# DRIVER_8_MOTOR_MEGA_DISTANCE_SENSOR_V1_0.net
KiCad netlist of a schematic drawn in EAGLE
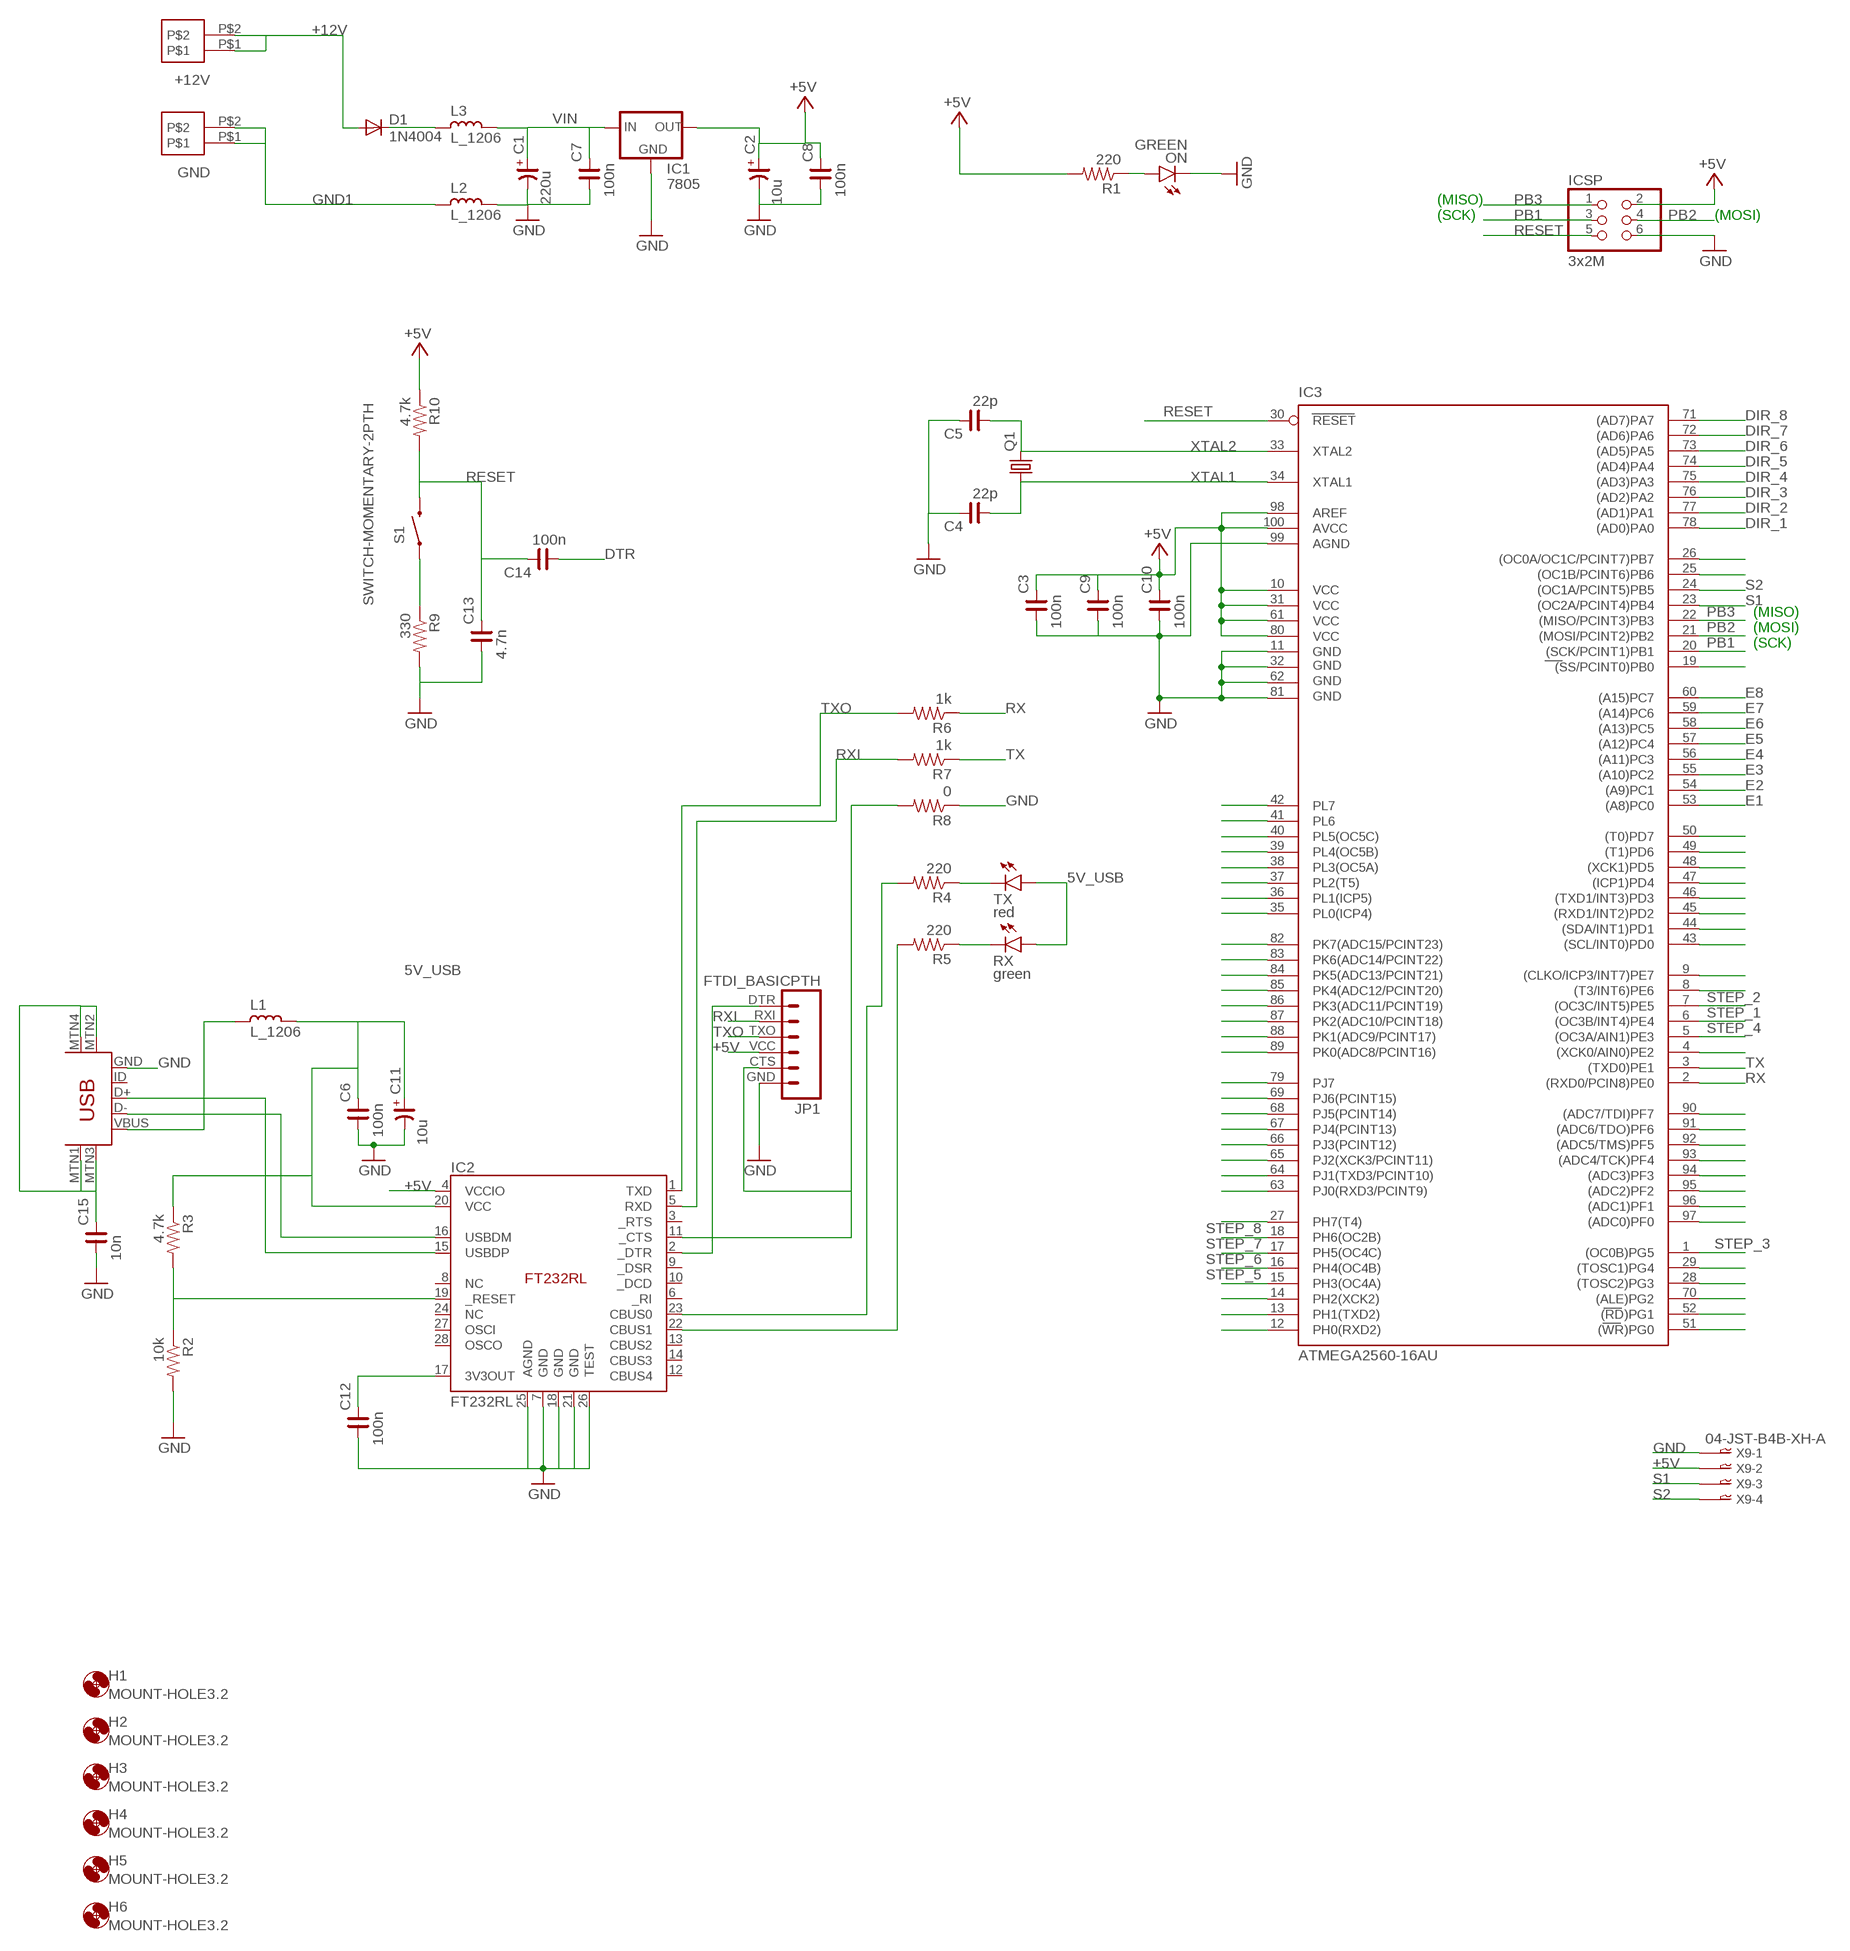
[diagram p0: schematic, sheet 1, part 1 of 2]
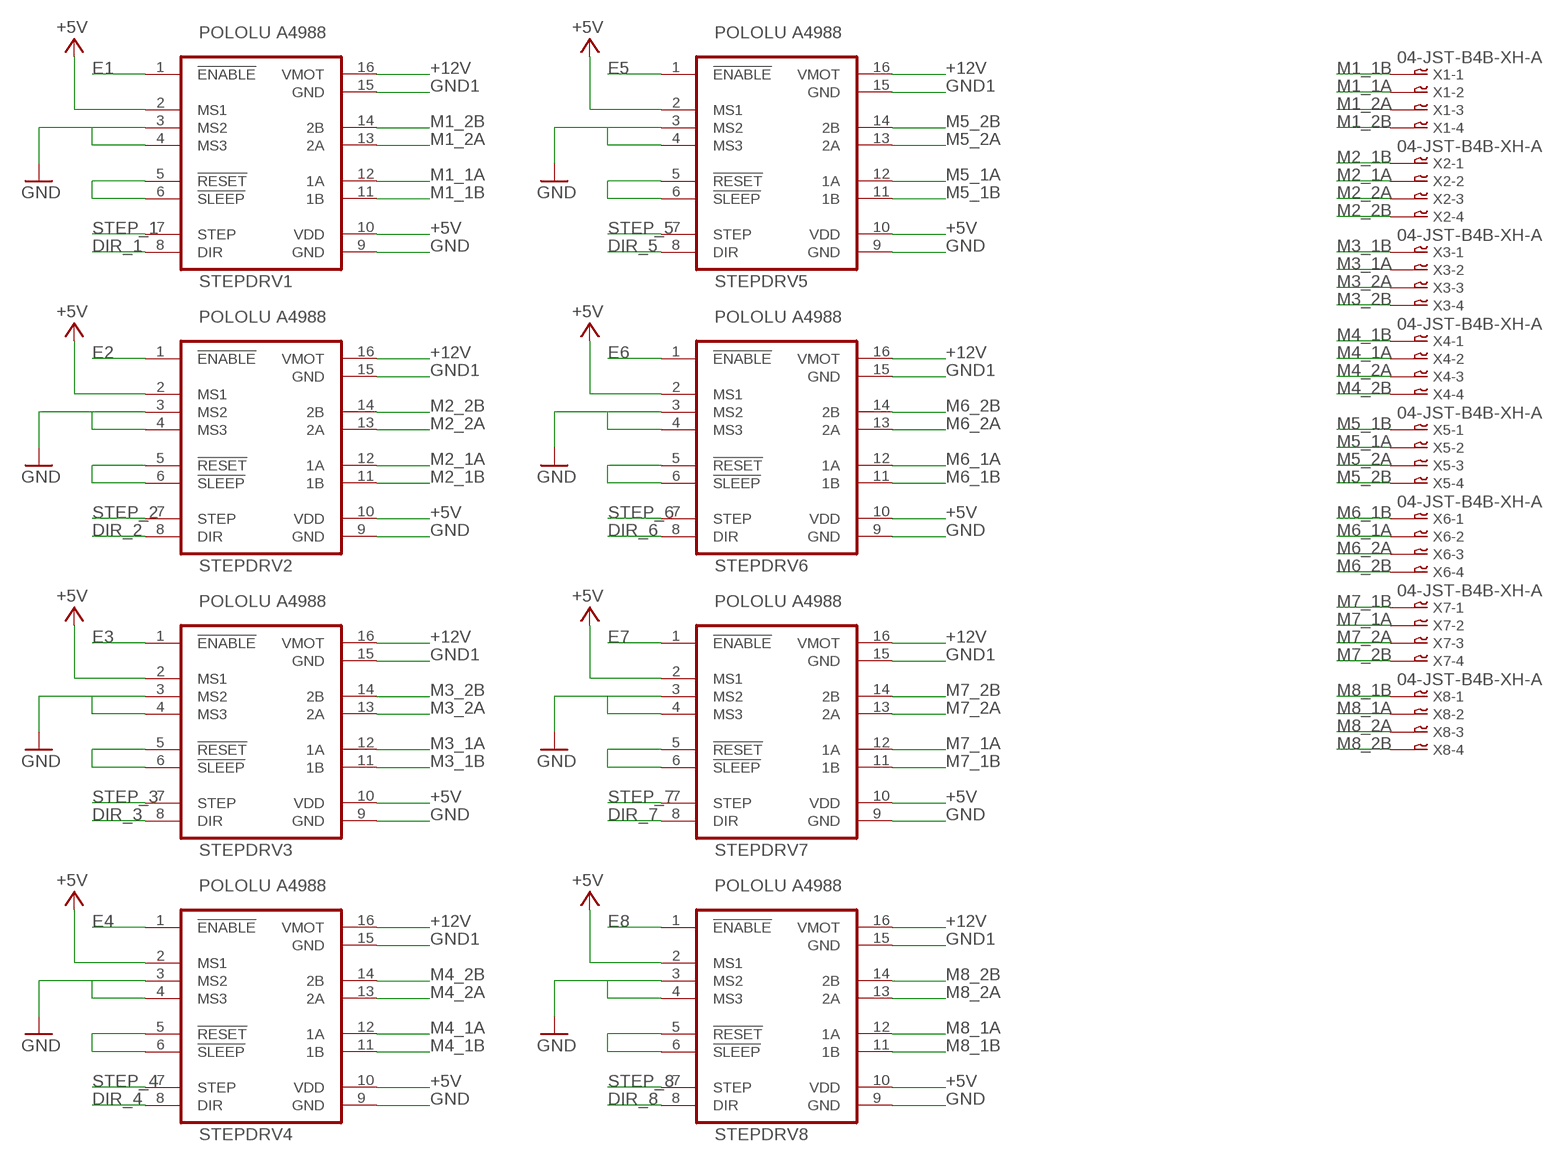
[diagram p1: schematic, sheet 1, part 2 of 2]

(export (version "E")
  (design (tool "Eeschema 10.0.6"))
  (components
    (comp (ref "+12V")
      (value "SCREW_T_10MM")
      (footprint "eagle-import:SCREW_T_10MM")
      (libsource (lib "eagle-import") (part "SCREW_T_10MM"))
    )
    (comp (ref "C1")
      (value "220u")
      (footprint "eagle-import:CE-050X100")
      (libsource (lib "eagle-import") (part "CP_E-050X100"))
    )
    (comp (ref "C2")
      (value "10u")
      (footprint "eagle-import:CE-050X100")
      (libsource (lib "eagle-import") (part "CP_E-050X100"))
    )
    (comp (ref "C3")
      (value "100n")
      (footprint "eagle-import:C050-075X030")
      (libsource (lib "eagle-import") (part "C_C050-075X030"))
    )
    (comp (ref "C4")
      (value "22p")
      (footprint "eagle-import:C050-075X030")
      (libsource (lib "eagle-import") (part "C_C050-075X030"))
    )
    (comp (ref "C5")
      (value "22p")
      (footprint "eagle-import:C050-075X030")
      (libsource (lib "eagle-import") (part "C_C050-075X030"))
    )
    (comp (ref "C6")
      (value "100n")
      (footprint "eagle-import:C050-075X030")
      (libsource (lib "eagle-import") (part "C_C050-075X030"))
    )
    (comp (ref "C7")
      (value "100n")
      (footprint "eagle-import:C050-075X030")
      (libsource (lib "eagle-import") (part "C_C050-075X030"))
    )
    (comp (ref "C8")
      (value "100n")
      (footprint "eagle-import:C050-075X030")
      (libsource (lib "eagle-import") (part "C_C050-075X030"))
    )
    (comp (ref "C9")
      (value "100n")
      (footprint "eagle-import:C050-075X030")
      (libsource (lib "eagle-import") (part "C_C050-075X030"))
    )
    (comp (ref "C10")
      (value "100n")
      (footprint "eagle-import:C050-075X030")
      (libsource (lib "eagle-import") (part "C_C050-075X030"))
    )
    (comp (ref "C11")
      (value "10u")
      (footprint "eagle-import:CE-025X060")
      (libsource (lib "eagle-import") (part "CP_E-025X060"))
    )
    (comp (ref "C12")
      (value "100n")
      (footprint "eagle-import:C050-075X030")
      (libsource (lib "eagle-import") (part "C_C050-075X030"))
    )
    (comp (ref "C13")
      (value "4.7n")
      (footprint "eagle-import:C050-075X030")
      (libsource (lib "eagle-import") (part "C_C050-075X030"))
    )
    (comp (ref "C14")
      (value "100n")
      (footprint "eagle-import:C050-075X030")
      (libsource (lib "eagle-import") (part "C_C050-075X030"))
    )
    (comp (ref "C15")
      (value "10n")
      (footprint "eagle-import:C050-075X030")
      (libsource (lib "eagle-import") (part "C_C050-075X030"))
    )
    (comp (ref "D1")
      (value "1N4004")
      (footprint "eagle-import:DO41-10")
      (libsource (lib "eagle-import") (part "1N4004"))
    )
    (comp (ref "GND")
      (value "SCREW_T_10MM")
      (footprint "eagle-import:SCREW_T_10MM")
      (libsource (lib "eagle-import") (part "SCREW_T_10MM"))
    )
    (comp (ref "H1")
      (value "MOUNT-HOLE3.2")
      (footprint "eagle-import:3,2")
      (libsource (lib "eagle-import") (part "MOUNT-HOLE3.2"))
    )
    (comp (ref "H2")
      (value "MOUNT-HOLE3.2")
      (footprint "eagle-import:3,2")
      (libsource (lib "eagle-import") (part "MOUNT-HOLE3.2"))
    )
    (comp (ref "H3")
      (value "MOUNT-HOLE3.2")
      (footprint "eagle-import:3,2")
      (libsource (lib "eagle-import") (part "MOUNT-HOLE3.2"))
    )
    (comp (ref "H4")
      (value "MOUNT-HOLE3.2")
      (footprint "eagle-import:3,2")
      (libsource (lib "eagle-import") (part "MOUNT-HOLE3.2"))
    )
    (comp (ref "H5")
      (value "MOUNT-HOLE3.2")
      (footprint "eagle-import:3,2")
      (libsource (lib "eagle-import") (part "MOUNT-HOLE3.2"))
    )
    (comp (ref "H6")
      (value "MOUNT-HOLE3.2")
      (footprint "eagle-import:3,2")
      (libsource (lib "eagle-import") (part "MOUNT-HOLE3.2"))
    )
    (comp (ref "IC1")
      (value "7805")
      (footprint "eagle-import:TO-220-ALT")
      (libsource (lib "eagle-import") (part "V_REG_78XX-TO-220"))
    )
    (comp (ref "IC2")
      (value "FT232RL")
      (footprint "eagle-import:SSOP-28")
      (libsource (lib "eagle-import") (part "FT232RL"))
    )
    (comp (ref "IC3")
      (value "ATMEGA2560-16AU")
      (footprint "eagle-import:TQFP100")
      (libsource (lib "eagle-import") (part "ATMEGA2560AU2560-16"))
    )
    (comp (ref "ICSP")
      (value "3x2M")
      (footprint "eagle-import:2X03")
      (libsource (lib "eagle-import") (part "PINHD-2X3"))
    )
    (comp (ref "JP1")
      (value "FTDI_BASICPTH")
      (footprint "eagle-import:FTDI_BASIC")
      (libsource (lib "eagle-import") (part "FTDI_BASICPTH"))
    )
    (comp (ref "L1")
      (value "L_1206")
      (footprint "eagle-import:L1206")
      (libsource (lib "eagle-import") (part "L_1206"))
    )
    (comp (ref "L2")
      (value "L_1206")
      (footprint "eagle-import:L1206")
      (libsource (lib "eagle-import") (part "L_1206"))
    )
    (comp (ref "L3")
      (value "L_1206")
      (footprint "eagle-import:L1206")
      (libsource (lib "eagle-import") (part "L_1206"))
    )
    (comp (ref "ON")
      (value "GREEN")
      (footprint "eagle-import:LED3MM")
      (libsource (lib "eagle-import") (part "LED3MM"))
    )
    (comp (ref "Q1")
      (value "CRYSTALHC49S")
      (footprint "eagle-import:HC49_S")
      (libsource (lib "eagle-import") (part "CRYSTALHC49S"))
    )
    (comp (ref "R1")
      (value "220")
      (footprint "eagle-import:0805")
      (libsource (lib "eagle-import") (part "0.75OHM1/4W1%(0805)"))
    )
    (comp (ref "R2")
      (value "10k")
      (footprint "eagle-import:0805")
      (libsource (lib "eagle-import") (part "0.75OHM1/4W1%(0805)"))
    )
    (comp (ref "R3")
      (value "4.7k")
      (footprint "eagle-import:0805")
      (libsource (lib "eagle-import") (part "0.75OHM1/4W1%(0805)"))
    )
    (comp (ref "R4")
      (value "220")
      (footprint "eagle-import:0805")
      (libsource (lib "eagle-import") (part "0.75OHM1/4W1%(0805)"))
    )
    (comp (ref "R5")
      (value "220")
      (footprint "eagle-import:0805")
      (libsource (lib "eagle-import") (part "0.75OHM1/4W1%(0805)"))
    )
    (comp (ref "R6")
      (value "1k")
      (footprint "eagle-import:0805")
      (libsource (lib "eagle-import") (part "0.75OHM1/4W1%(0805)"))
    )
    (comp (ref "R7")
      (value "1k")
      (footprint "eagle-import:0805")
      (libsource (lib "eagle-import") (part "0.75OHM1/4W1%(0805)"))
    )
    (comp (ref "R8")
      (value "0")
      (footprint "eagle-import:0805")
      (libsource (lib "eagle-import") (part "0.75OHM1/4W1%(0805)"))
    )
    (comp (ref "R9")
      (value "330")
      (footprint "eagle-import:0805")
      (libsource (lib "eagle-import") (part "0.75OHM1/4W1%(0805)"))
    )
    (comp (ref "R10")
      (value "4.7k")
      (footprint "eagle-import:0805")
      (libsource (lib "eagle-import") (part "0.75OHM1/4W1%(0805)"))
    )
    (comp (ref "RX")
      (value "green")
      (footprint "eagle-import:LED3MM")
      (libsource (lib "eagle-import") (part "LED3MM"))
    )
    (comp (ref "S1")
      (value "SWITCH-MOMENTARY-2PTH")
      (footprint "eagle-import:TACTILE-PTH")
      (libsource (lib "eagle-import") (part "SWITCH-MOMENTARY-2PTH"))
    )
    (comp (ref "STEPDRV1")
      (value "POLOLU A4988")
      (footprint "eagle-import:POLOLULU2128")
      (libsource (lib "eagle-import") (part "POLOLULU2128"))
    )
    (comp (ref "STEPDRV2")
      (value "POLOLU A4988")
      (footprint "eagle-import:POLOLULU2128")
      (libsource (lib "eagle-import") (part "POLOLULU2128"))
    )
    (comp (ref "STEPDRV3")
      (value "POLOLU A4988")
      (footprint "eagle-import:POLOLULU2128")
      (libsource (lib "eagle-import") (part "POLOLULU2128"))
    )
    (comp (ref "STEPDRV4")
      (value "POLOLU A4988")
      (footprint "eagle-import:POLOLULU2128")
      (libsource (lib "eagle-import") (part "POLOLULU2128"))
    )
    (comp (ref "STEPDRV5")
      (value "POLOLU A4988")
      (footprint "eagle-import:POLOLULU2128")
      (libsource (lib "eagle-import") (part "POLOLULU2128"))
    )
    (comp (ref "STEPDRV6")
      (value "POLOLU A4988")
      (footprint "eagle-import:POLOLULU2128")
      (libsource (lib "eagle-import") (part "POLOLULU2128"))
    )
    (comp (ref "STEPDRV7")
      (value "POLOLU A4988")
      (footprint "eagle-import:POLOLULU2128")
      (libsource (lib "eagle-import") (part "POLOLULU2128"))
    )
    (comp (ref "STEPDRV8")
      (value "POLOLU A4988")
      (footprint "eagle-import:POLOLULU2128")
      (libsource (lib "eagle-import") (part "POLOLULU2128"))
    )
    (comp (ref "TX")
      (value "red")
      (footprint "eagle-import:LED3MM")
      (libsource (lib "eagle-import") (part "LED3MM"))
    )
    (comp (ref "U$1")
      (value "USB-MINIB-5PIN")
      (footprint "eagle-import:USB-MINIB")
      (libsource (lib "eagle-import") (part "USB-MINIB-5PIN"))
    )
    (comp (ref "X1")
      (value "04-JST-B4B-XH-A")
      (footprint "eagle-import:B4B-XH")
      (libsource (lib "eagle-import") (part "04-JST-B4B-XH-A"))
    )
    (comp (ref "X2")
      (value "04-JST-B4B-XH-A")
      (footprint "eagle-import:B4B-XH")
      (libsource (lib "eagle-import") (part "04-JST-B4B-XH-A"))
    )
    (comp (ref "X3")
      (value "04-JST-B4B-XH-A")
      (footprint "eagle-import:B4B-XH")
      (libsource (lib "eagle-import") (part "04-JST-B4B-XH-A"))
    )
    (comp (ref "X4")
      (value "04-JST-B4B-XH-A")
      (footprint "eagle-import:B4B-XH")
      (libsource (lib "eagle-import") (part "04-JST-B4B-XH-A"))
    )
    (comp (ref "X5")
      (value "04-JST-B4B-XH-A")
      (footprint "eagle-import:B4B-XH")
      (libsource (lib "eagle-import") (part "04-JST-B4B-XH-A"))
    )
    (comp (ref "X6")
      (value "04-JST-B4B-XH-A")
      (footprint "eagle-import:B4B-XH")
      (libsource (lib "eagle-import") (part "04-JST-B4B-XH-A"))
    )
    (comp (ref "X7")
      (value "04-JST-B4B-XH-A")
      (footprint "eagle-import:B4B-XH")
      (libsource (lib "eagle-import") (part "04-JST-B4B-XH-A"))
    )
    (comp (ref "X8")
      (value "04-JST-B4B-XH-A")
      (footprint "eagle-import:B4B-XH")
      (libsource (lib "eagle-import") (part "04-JST-B4B-XH-A"))
    )
    (comp (ref "X9")
      (value "04-JST-B4B-XH-A")
      (footprint "eagle-import:B4B-XH")
      (libsource (lib "eagle-import") (part "04-JST-B4B-XH-A"))
    )
  )
  (nets
    (net (code "1") (name "+5V") (class "Default")
      (node (ref "C10") (pin "2") (pinfunction "2_2") (pintype "passive"))
      (node (ref "C2") (pin "+") (pinfunction "+_+") (pintype "passive"))
      (node (ref "C3") (pin "2") (pinfunction "2_2") (pintype "passive"))
      (node (ref "C8") (pin "2") (pinfunction "2_2") (pintype "passive"))
      (node (ref "C9") (pin "2") (pinfunction "2_2") (pintype "passive"))
      (node (ref "IC1") (pin "OUT") (pinfunction "OUT_OUT") (pintype "output"))
      (node (ref "IC2") (pin "4") (pinfunction "VCCIO_4") (pintype "power_in"))
      (node (ref "IC3") (pin "10") (pinfunction "VCC_10") (pintype "power_in"))
      (node (ref "IC3") (pin "100") (pinfunction "AVCC_100") (pintype "power_in"))
      (node (ref "IC3") (pin "31") (pinfunction "VCC1_31") (pintype "power_in"))
      (node (ref "IC3") (pin "61") (pinfunction "VCC2_61") (pintype "power_in"))
      (node (ref "IC3") (pin "80") (pinfunction "VCC3_80") (pintype "power_in"))
      (node (ref "IC3") (pin "98") (pinfunction "AREF_98") (pintype "bidirectional"))
      (node (ref "ICSP") (pin "2") (pinfunction "2_2") (pintype "passive"))
      (node (ref "JP1") (pin "VCC") (pinfunction "4_VCC") (pintype "passive"))
      (node (ref "R1") (pin "2") (pinfunction "2_2") (pintype "passive"))
      (node (ref "R10") (pin "1") (pinfunction "1_1") (pintype "passive"))
      (node (ref "STEPDRV1") (pin "10") (pinfunction "VDD_10") (pintype "power_in"))
      (node (ref "STEPDRV1") (pin "2") (pinfunction "MS1_2") (pintype "input"))
      (node (ref "STEPDRV2") (pin "10") (pinfunction "VDD_10") (pintype "power_in"))
      (node (ref "STEPDRV2") (pin "2") (pinfunction "MS1_2") (pintype "input"))
      (node (ref "STEPDRV3") (pin "10") (pinfunction "VDD_10") (pintype "power_in"))
      (node (ref "STEPDRV3") (pin "2") (pinfunction "MS1_2") (pintype "input"))
      (node (ref "STEPDRV4") (pin "10") (pinfunction "VDD_10") (pintype "power_in"))
      (node (ref "STEPDRV4") (pin "2") (pinfunction "MS1_2") (pintype "input"))
      (node (ref "STEPDRV5") (pin "10") (pinfunction "VDD_10") (pintype "power_in"))
      (node (ref "STEPDRV5") (pin "2") (pinfunction "MS1_2") (pintype "input"))
      (node (ref "STEPDRV6") (pin "10") (pinfunction "VDD_10") (pintype "power_in"))
      (node (ref "STEPDRV6") (pin "2") (pinfunction "MS1_2") (pintype "input"))
      (node (ref "STEPDRV7") (pin "10") (pinfunction "VDD_10") (pintype "power_in"))
      (node (ref "STEPDRV7") (pin "2") (pinfunction "MS1_2") (pintype "input"))
      (node (ref "STEPDRV8") (pin "10") (pinfunction "VDD_10") (pintype "power_in"))
      (node (ref "STEPDRV8") (pin "2") (pinfunction "MS1_2") (pintype "input"))
      (node (ref "X9") (pin "P$2") (pinfunction "1_P$2") (pintype "passive"))
    )
    (net (code "2") (name "/+12V") (class "Default")
      (node (ref "+12V") (pin "P$1") (pinfunction "P$1_P$1") (pintype "bidirectional"))
      (node (ref "+12V") (pin "P$2") (pinfunction "P$2_P$2") (pintype "bidirectional"))
      (node (ref "D1") (pin "A") (pinfunction "A_A") (pintype "passive"))
      (node (ref "STEPDRV1") (pin "16") (pinfunction "VMOT_16") (pintype "power_in"))
      (node (ref "STEPDRV2") (pin "16") (pinfunction "VMOT_16") (pintype "power_in"))
      (node (ref "STEPDRV3") (pin "16") (pinfunction "VMOT_16") (pintype "power_in"))
      (node (ref "STEPDRV4") (pin "16") (pinfunction "VMOT_16") (pintype "power_in"))
      (node (ref "STEPDRV5") (pin "16") (pinfunction "VMOT_16") (pintype "power_in"))
      (node (ref "STEPDRV6") (pin "16") (pinfunction "VMOT_16") (pintype "power_in"))
      (node (ref "STEPDRV7") (pin "16") (pinfunction "VMOT_16") (pintype "power_in"))
      (node (ref "STEPDRV8") (pin "16") (pinfunction "VMOT_16") (pintype "power_in"))
    )
    (net (code "3") (name "/5V_USB") (class "Default")
      (node (ref "C11") (pin "+") (pinfunction "+_+") (pintype "passive"))
      (node (ref "C6") (pin "2") (pinfunction "2_2") (pintype "passive"))
      (node (ref "IC2") (pin "20") (pinfunction "VCC_20") (pintype "power_in"))
      (node (ref "L1") (pin "1") (pinfunction "1_1") (pintype "passive"))
      (node (ref "R3") (pin "1") (pinfunction "1_1") (pintype "passive"))
      (node (ref "RX") (pin "A") (pinfunction "A_A") (pintype "passive"))
      (node (ref "TX") (pin "A") (pinfunction "A_A") (pintype "passive"))
    )
    (net (code "4") (name "/DIR_1") (class "Default")
      (node (ref "IC3") (pin "78") (pinfunction "(AD0)PA0_78") (pintype "bidirectional"))
      (node (ref "STEPDRV1") (pin "8") (pinfunction "DIR_8") (pintype "input"))
    )
    (net (code "5") (name "/DIR_2") (class "Default")
      (node (ref "IC3") (pin "77") (pinfunction "(AD1)PA1_77") (pintype "bidirectional"))
      (node (ref "STEPDRV2") (pin "8") (pinfunction "DIR_8") (pintype "input"))
    )
    (net (code "6") (name "/DIR_3") (class "Default")
      (node (ref "IC3") (pin "76") (pinfunction "(AD2)PA2_76") (pintype "bidirectional"))
      (node (ref "STEPDRV3") (pin "8") (pinfunction "DIR_8") (pintype "input"))
    )
    (net (code "7") (name "/DIR_4") (class "Default")
      (node (ref "IC3") (pin "75") (pinfunction "(AD3)PA3_75") (pintype "bidirectional"))
      (node (ref "STEPDRV4") (pin "8") (pinfunction "DIR_8") (pintype "input"))
    )
    (net (code "8") (name "/DIR_5") (class "Default")
      (node (ref "IC3") (pin "74") (pinfunction "(AD4)PA4_74") (pintype "bidirectional"))
      (node (ref "STEPDRV5") (pin "8") (pinfunction "DIR_8") (pintype "input"))
    )
    (net (code "9") (name "/DIR_6") (class "Default")
      (node (ref "IC3") (pin "73") (pinfunction "(AD5)PA5_73") (pintype "bidirectional"))
      (node (ref "STEPDRV6") (pin "8") (pinfunction "DIR_8") (pintype "input"))
    )
    (net (code "10") (name "/DIR_7") (class "Default")
      (node (ref "IC3") (pin "72") (pinfunction "(AD6)PA6_72") (pintype "bidirectional"))
      (node (ref "STEPDRV7") (pin "8") (pinfunction "DIR_8") (pintype "input"))
    )
    (net (code "11") (name "/DIR_8") (class "Default")
      (node (ref "IC3") (pin "71") (pinfunction "(AD7)PA7_71") (pintype "bidirectional"))
      (node (ref "STEPDRV8") (pin "8") (pinfunction "DIR_8") (pintype "input"))
    )
    (net (code "12") (name "/DTR") (class "Default")
      (node (ref "C14") (pin "1") (pinfunction "1_1") (pintype "passive"))
      (node (ref "IC2") (pin "2") (pinfunction "_DTR_2") (pintype "input"))
      (node (ref "JP1") (pin "DTR") (pinfunction "1_DTR") (pintype "passive"))
    )
    (net (code "13") (name "/E1") (class "Default")
      (node (ref "IC3") (pin "53") (pinfunction "(A8)PC0_53") (pintype "bidirectional"))
      (node (ref "STEPDRV1") (pin "1") (pinfunction "~{ENABLE}_1") (pintype "input"))
    )
    (net (code "14") (name "/E2") (class "Default")
      (node (ref "IC3") (pin "54") (pinfunction "(A9)PC1_54") (pintype "bidirectional"))
      (node (ref "STEPDRV2") (pin "1") (pinfunction "~{ENABLE}_1") (pintype "input"))
    )
    (net (code "15") (name "/E3") (class "Default")
      (node (ref "IC3") (pin "55") (pinfunction "(A10)PC2_55") (pintype "bidirectional"))
      (node (ref "STEPDRV3") (pin "1") (pinfunction "~{ENABLE}_1") (pintype "input"))
    )
    (net (code "16") (name "/E4") (class "Default")
      (node (ref "IC3") (pin "56") (pinfunction "(A11)PC3_56") (pintype "bidirectional"))
      (node (ref "STEPDRV4") (pin "1") (pinfunction "~{ENABLE}_1") (pintype "input"))
    )
    (net (code "17") (name "/E5") (class "Default")
      (node (ref "IC3") (pin "57") (pinfunction "(A12)PC4_57") (pintype "bidirectional"))
      (node (ref "STEPDRV5") (pin "1") (pinfunction "~{ENABLE}_1") (pintype "input"))
    )
    (net (code "18") (name "/E6") (class "Default")
      (node (ref "IC3") (pin "58") (pinfunction "(A13)PC5_58") (pintype "bidirectional"))
      (node (ref "STEPDRV6") (pin "1") (pinfunction "~{ENABLE}_1") (pintype "input"))
    )
    (net (code "19") (name "/E7") (class "Default")
      (node (ref "IC3") (pin "59") (pinfunction "(A14)PC6_59") (pintype "bidirectional"))
      (node (ref "STEPDRV7") (pin "1") (pinfunction "~{ENABLE}_1") (pintype "input"))
    )
    (net (code "20") (name "/E8") (class "Default")
      (node (ref "IC3") (pin "60") (pinfunction "(A15)PC7_60") (pintype "bidirectional"))
      (node (ref "STEPDRV8") (pin "1") (pinfunction "~{ENABLE}_1") (pintype "input"))
    )
    (net (code "21") (name "/GND1") (class "Default")
      (node (ref "GND") (pin "P$1") (pinfunction "P$1_P$1") (pintype "bidirectional"))
      (node (ref "GND") (pin "P$2") (pinfunction "P$2_P$2") (pintype "bidirectional"))
      (node (ref "L2") (pin "2") (pinfunction "2_2") (pintype "passive"))
      (node (ref "STEPDRV1") (pin "15") (pinfunction "GND_15") (pintype "power_in"))
      (node (ref "STEPDRV2") (pin "15") (pinfunction "GND_15") (pintype "power_in"))
      (node (ref "STEPDRV3") (pin "15") (pinfunction "GND_15") (pintype "power_in"))
      (node (ref "STEPDRV4") (pin "15") (pinfunction "GND_15") (pintype "power_in"))
      (node (ref "STEPDRV5") (pin "15") (pinfunction "GND_15") (pintype "power_in"))
      (node (ref "STEPDRV6") (pin "15") (pinfunction "GND_15") (pintype "power_in"))
      (node (ref "STEPDRV7") (pin "15") (pinfunction "GND_15") (pintype "power_in"))
      (node (ref "STEPDRV8") (pin "15") (pinfunction "GND_15") (pintype "power_in"))
    )
    (net (code "22") (name "/M1_1A") (class "Default")
      (node (ref "STEPDRV1") (pin "12") (pinfunction "1A_12") (pintype "output"))
      (node (ref "X1") (pin "P$2") (pinfunction "1_P$2") (pintype "passive"))
    )
    (net (code "23") (name "/M1_1B") (class "Default")
      (node (ref "STEPDRV1") (pin "11") (pinfunction "1B_11") (pintype "output"))
      (node (ref "X1") (pin "P$1") (pinfunction "1_P$1") (pintype "passive"))
    )
    (net (code "24") (name "/M1_2A") (class "Default")
      (node (ref "STEPDRV1") (pin "13") (pinfunction "2A_13") (pintype "output"))
      (node (ref "X1") (pin "P$3") (pinfunction "1_P$3") (pintype "passive"))
    )
    (net (code "25") (name "/M1_2B") (class "Default")
      (node (ref "STEPDRV1") (pin "14") (pinfunction "2B_14") (pintype "output"))
      (node (ref "X1") (pin "P$4") (pinfunction "1_P$4") (pintype "passive"))
    )
    (net (code "26") (name "/M2_1A") (class "Default")
      (node (ref "STEPDRV2") (pin "12") (pinfunction "1A_12") (pintype "output"))
      (node (ref "X2") (pin "P$2") (pinfunction "1_P$2") (pintype "passive"))
    )
    (net (code "27") (name "/M2_1B") (class "Default")
      (node (ref "STEPDRV2") (pin "11") (pinfunction "1B_11") (pintype "output"))
      (node (ref "X2") (pin "P$1") (pinfunction "1_P$1") (pintype "passive"))
    )
    (net (code "28") (name "/M2_2A") (class "Default")
      (node (ref "STEPDRV2") (pin "13") (pinfunction "2A_13") (pintype "output"))
      (node (ref "X2") (pin "P$3") (pinfunction "1_P$3") (pintype "passive"))
    )
    (net (code "29") (name "/M2_2B") (class "Default")
      (node (ref "STEPDRV2") (pin "14") (pinfunction "2B_14") (pintype "output"))
      (node (ref "X2") (pin "P$4") (pinfunction "1_P$4") (pintype "passive"))
    )
    (net (code "30") (name "/M3_1A") (class "Default")
      (node (ref "STEPDRV3") (pin "12") (pinfunction "1A_12") (pintype "output"))
      (node (ref "X3") (pin "P$2") (pinfunction "1_P$2") (pintype "passive"))
    )
    (net (code "31") (name "/M3_1B") (class "Default")
      (node (ref "STEPDRV3") (pin "11") (pinfunction "1B_11") (pintype "output"))
      (node (ref "X3") (pin "P$1") (pinfunction "1_P$1") (pintype "passive"))
    )
    (net (code "32") (name "/M3_2A") (class "Default")
      (node (ref "STEPDRV3") (pin "13") (pinfunction "2A_13") (pintype "output"))
      (node (ref "X3") (pin "P$3") (pinfunction "1_P$3") (pintype "passive"))
    )
    (net (code "33") (name "/M3_2B") (class "Default")
      (node (ref "STEPDRV3") (pin "14") (pinfunction "2B_14") (pintype "output"))
      (node (ref "X3") (pin "P$4") (pinfunction "1_P$4") (pintype "passive"))
    )
    (net (code "34") (name "/M4_1A") (class "Default")
      (node (ref "STEPDRV4") (pin "12") (pinfunction "1A_12") (pintype "output"))
      (node (ref "X4") (pin "P$2") (pinfunction "1_P$2") (pintype "passive"))
    )
    (net (code "35") (name "/M4_1B") (class "Default")
      (node (ref "STEPDRV4") (pin "11") (pinfunction "1B_11") (pintype "output"))
      (node (ref "X4") (pin "P$1") (pinfunction "1_P$1") (pintype "passive"))
    )
    (net (code "36") (name "/M4_2A") (class "Default")
      (node (ref "STEPDRV4") (pin "13") (pinfunction "2A_13") (pintype "output"))
      (node (ref "X4") (pin "P$3") (pinfunction "1_P$3") (pintype "passive"))
    )
    (net (code "37") (name "/M4_2B") (class "Default")
      (node (ref "STEPDRV4") (pin "14") (pinfunction "2B_14") (pintype "output"))
      (node (ref "X4") (pin "P$4") (pinfunction "1_P$4") (pintype "passive"))
    )
    (net (code "38") (name "/M5_1A") (class "Default")
      (node (ref "STEPDRV5") (pin "12") (pinfunction "1A_12") (pintype "output"))
      (node (ref "X5") (pin "P$2") (pinfunction "1_P$2") (pintype "passive"))
    )
    (net (code "39") (name "/M5_1B") (class "Default")
      (node (ref "STEPDRV5") (pin "11") (pinfunction "1B_11") (pintype "output"))
      (node (ref "X5") (pin "P$1") (pinfunction "1_P$1") (pintype "passive"))
    )
    (net (code "40") (name "/M5_2A") (class "Default")
      (node (ref "STEPDRV5") (pin "13") (pinfunction "2A_13") (pintype "output"))
      (node (ref "X5") (pin "P$3") (pinfunction "1_P$3") (pintype "passive"))
    )
    (net (code "41") (name "/M5_2B") (class "Default")
      (node (ref "STEPDRV5") (pin "14") (pinfunction "2B_14") (pintype "output"))
      (node (ref "X5") (pin "P$4") (pinfunction "1_P$4") (pintype "passive"))
    )
    (net (code "42") (name "/M6_1A") (class "Default")
      (node (ref "STEPDRV6") (pin "12") (pinfunction "1A_12") (pintype "output"))
      (node (ref "X6") (pin "P$2") (pinfunction "1_P$2") (pintype "passive"))
    )
    (net (code "43") (name "/M6_1B") (class "Default")
      (node (ref "STEPDRV6") (pin "11") (pinfunction "1B_11") (pintype "output"))
      (node (ref "X6") (pin "P$1") (pinfunction "1_P$1") (pintype "passive"))
    )
    (net (code "44") (name "/M6_2A") (class "Default")
      (node (ref "STEPDRV6") (pin "13") (pinfunction "2A_13") (pintype "output"))
      (node (ref "X6") (pin "P$3") (pinfunction "1_P$3") (pintype "passive"))
    )
    (net (code "45") (name "/M6_2B") (class "Default")
      (node (ref "STEPDRV6") (pin "14") (pinfunction "2B_14") (pintype "output"))
      (node (ref "X6") (pin "P$4") (pinfunction "1_P$4") (pintype "passive"))
    )
    (net (code "46") (name "/M7_1A") (class "Default")
      (node (ref "STEPDRV7") (pin "12") (pinfunction "1A_12") (pintype "output"))
      (node (ref "X7") (pin "P$2") (pinfunction "1_P$2") (pintype "passive"))
    )
    (net (code "47") (name "/M7_1B") (class "Default")
      (node (ref "STEPDRV7") (pin "11") (pinfunction "1B_11") (pintype "output"))
      (node (ref "X7") (pin "P$1") (pinfunction "1_P$1") (pintype "passive"))
    )
    (net (code "48") (name "/M7_2A") (class "Default")
      (node (ref "STEPDRV7") (pin "13") (pinfunction "2A_13") (pintype "output"))
      (node (ref "X7") (pin "P$3") (pinfunction "1_P$3") (pintype "passive"))
    )
    (net (code "49") (name "/M7_2B") (class "Default")
      (node (ref "STEPDRV7") (pin "14") (pinfunction "2B_14") (pintype "output"))
      (node (ref "X7") (pin "P$4") (pinfunction "1_P$4") (pintype "passive"))
    )
    (net (code "50") (name "/M8_1A") (class "Default")
      (node (ref "STEPDRV8") (pin "12") (pinfunction "1A_12") (pintype "output"))
      (node (ref "X8") (pin "P$2") (pinfunction "1_P$2") (pintype "passive"))
    )
    (net (code "51") (name "/M8_1B") (class "Default")
      (node (ref "STEPDRV8") (pin "11") (pinfunction "1B_11") (pintype "output"))
      (node (ref "X8") (pin "P$1") (pinfunction "1_P$1") (pintype "passive"))
    )
    (net (code "52") (name "/M8_2A") (class "Default")
      (node (ref "STEPDRV8") (pin "13") (pinfunction "2A_13") (pintype "output"))
      (node (ref "X8") (pin "P$3") (pinfunction "1_P$3") (pintype "passive"))
    )
    (net (code "53") (name "/M8_2B") (class "Default")
      (node (ref "STEPDRV8") (pin "14") (pinfunction "2B_14") (pintype "output"))
      (node (ref "X8") (pin "P$4") (pinfunction "1_P$4") (pintype "passive"))
    )
    (net (code "54") (name "/PB1") (class "Default")
      (node (ref "IC3") (pin "20") (pinfunction "(SCK/PCINT1)PB1_20") (pintype "bidirectional"))
      (node (ref "ICSP") (pin "3") (pinfunction "3_3") (pintype "passive"))
    )
    (net (code "55") (name "/PB2") (class "Default")
      (node (ref "IC3") (pin "21") (pinfunction "(MOSI/PCINT2)PB2_21") (pintype "bidirectional"))
      (node (ref "ICSP") (pin "4") (pinfunction "4_4") (pintype "passive"))
    )
    (net (code "56") (name "/PB3") (class "Default")
      (node (ref "IC3") (pin "22") (pinfunction "(MISO/PCINT3)PB3_22") (pintype "bidirectional"))
      (node (ref "ICSP") (pin "1") (pinfunction "1_1") (pintype "passive"))
    )
    (net (code "57") (name "/RESET") (class "Default")
      (node (ref "C13") (pin "2") (pinfunction "2_2") (pintype "passive"))
      (node (ref "C14") (pin "2") (pinfunction "2_2") (pintype "passive"))
      (node (ref "IC3") (pin "30") (pinfunction "RESET_30") (pintype "input"))
      (node (ref "ICSP") (pin "5") (pinfunction "5_5") (pintype "passive"))
      (node (ref "R10") (pin "2") (pinfunction "2_2") (pintype "passive"))
      (node (ref "S1") (pin "3") (pinfunction "2_3") (pintype "passive"))
    )
    (net (code "58") (name "/RX") (class "Default")
      (node (ref "IC3") (pin "2") (pinfunction "(RXD0/PCIN8)PE0_2") (pintype "bidirectional"))
      (node (ref "R6") (pin "1") (pinfunction "1_1") (pintype "passive"))
    )
    (net (code "59") (name "/RXI") (class "Default")
      (node (ref "IC2") (pin "5") (pinfunction "RXD_5") (pintype "input"))
      (node (ref "JP1") (pin "RXI") (pinfunction "2_RXI") (pintype "passive"))
      (node (ref "R7") (pin "2") (pinfunction "2_2") (pintype "passive"))
    )
    (net (code "60") (name "/S1") (class "Default")
      (node (ref "IC3") (pin "23") (pinfunction "(OC2A/PCINT4)PB4_23") (pintype "bidirectional"))
      (node (ref "X9") (pin "P$3") (pinfunction "1_P$3") (pintype "passive"))
    )
    (net (code "61") (name "/S2") (class "Default")
      (node (ref "IC3") (pin "24") (pinfunction "(OC1A/PCINT5)PB5_24") (pintype "bidirectional"))
      (node (ref "X9") (pin "P$4") (pinfunction "1_P$4") (pintype "passive"))
    )
    (net (code "62") (name "/STEP_1") (class "Default")
      (node (ref "IC3") (pin "6") (pinfunction "(OC3B/INT4)PE4_6") (pintype "bidirectional"))
      (node (ref "STEPDRV1") (pin "7") (pinfunction "STEP_7") (pintype "input"))
    )
    (net (code "63") (name "/STEP_2") (class "Default")
      (node (ref "IC3") (pin "7") (pinfunction "(OC3C/INT5)PE5_7") (pintype "bidirectional"))
      (node (ref "STEPDRV2") (pin "7") (pinfunction "STEP_7") (pintype "input"))
    )
    (net (code "64") (name "/STEP_3") (class "Default")
      (node (ref "IC3") (pin "1") (pinfunction "(OC0B)PG5_1") (pintype "bidirectional"))
      (node (ref "STEPDRV3") (pin "7") (pinfunction "STEP_7") (pintype "input"))
    )
    (net (code "65") (name "/STEP_4") (class "Default")
      (node (ref "IC3") (pin "5") (pinfunction "(OC3A/AIN1)PE3_5") (pintype "bidirectional"))
      (node (ref "STEPDRV4") (pin "7") (pinfunction "STEP_7") (pintype "input"))
    )
    (net (code "66") (name "/STEP_5") (class "Default")
      (node (ref "IC3") (pin "15") (pinfunction "PH3(OC4A)_15") (pintype "bidirectional"))
      (node (ref "STEPDRV5") (pin "7") (pinfunction "STEP_7") (pintype "input"))
    )
    (net (code "67") (name "/STEP_6") (class "Default")
      (node (ref "IC3") (pin "16") (pinfunction "PH4(OC4B)_16") (pintype "bidirectional"))
      (node (ref "STEPDRV6") (pin "7") (pinfunction "STEP_7") (pintype "input"))
    )
    (net (code "68") (name "/STEP_7") (class "Default")
      (node (ref "IC3") (pin "17") (pinfunction "PH5(OC4C)_17") (pintype "bidirectional"))
      (node (ref "STEPDRV7") (pin "7") (pinfunction "STEP_7") (pintype "input"))
    )
    (net (code "69") (name "/STEP_8") (class "Default")
      (node (ref "IC3") (pin "18") (pinfunction "PH6(OC2B)_18") (pintype "bidirectional"))
      (node (ref "STEPDRV8") (pin "7") (pinfunction "STEP_7") (pintype "input"))
    )
    (net (code "70") (name "/TX") (class "Default")
      (node (ref "IC3") (pin "3") (pinfunction "(TXD0)PE1_3") (pintype "bidirectional"))
      (node (ref "R7") (pin "1") (pinfunction "1_1") (pintype "passive"))
    )
    (net (code "71") (name "/TXO") (class "Default")
      (node (ref "IC2") (pin "1") (pinfunction "TXD_1") (pintype "output"))
      (node (ref "JP1") (pin "TXO") (pinfunction "3_TXO") (pintype "passive"))
      (node (ref "R6") (pin "2") (pinfunction "2_2") (pintype "passive"))
    )
    (net (code "72") (name "/VIN") (class "Default")
      (node (ref "C1") (pin "+") (pinfunction "+_+") (pintype "passive"))
      (node (ref "C7") (pin "2") (pinfunction "2_2") (pintype "passive"))
      (node (ref "IC1") (pin "IN") (pinfunction "IN_IN") (pintype "input"))
      (node (ref "L3") (pin "1") (pinfunction "1_1") (pintype "passive"))
    )
    (net (code "73") (name "/XTAL1") (class "Default")
      (node (ref "C4") (pin "1") (pinfunction "1_1") (pintype "passive"))
      (node (ref "IC3") (pin "34") (pinfunction "XTAL1_34") (pintype "input"))
      (node (ref "Q1") (pin "1") (pinfunction "1_1") (pintype "passive"))
    )
    (net (code "74") (name "/XTAL2") (class "Default")
      (node (ref "C5") (pin "1") (pinfunction "1_1") (pintype "passive"))
      (node (ref "IC3") (pin "33") (pinfunction "XTAL2_33") (pintype "output"))
      (node (ref "Q1") (pin "2") (pinfunction "2_2") (pintype "passive"))
    )
    (net (code "75") (name "GND") (class "Default")
      (node (ref "C1") (pin "-") (pinfunction "-_-") (pintype "passive"))
      (node (ref "C10") (pin "1") (pinfunction "1_1") (pintype "passive"))
      (node (ref "C11") (pin "-") (pinfunction "-_-") (pintype "passive"))
      (node (ref "C12") (pin "1") (pinfunction "1_1") (pintype "passive"))
      (node (ref "C13") (pin "1") (pinfunction "1_1") (pintype "passive"))
      (node (ref "C15") (pin "1") (pinfunction "1_1") (pintype "passive"))
      (node (ref "C2") (pin "-") (pinfunction "-_-") (pintype "passive"))
      (node (ref "C3") (pin "1") (pinfunction "1_1") (pintype "passive"))
      (node (ref "C4") (pin "2") (pinfunction "2_2") (pintype "passive"))
      (node (ref "C5") (pin "2") (pinfunction "2_2") (pintype "passive"))
      (node (ref "C6") (pin "1") (pinfunction "1_1") (pintype "passive"))
      (node (ref "C7") (pin "1") (pinfunction "1_1") (pintype "passive"))
      (node (ref "C8") (pin "1") (pinfunction "1_1") (pintype "passive"))
      (node (ref "C9") (pin "1") (pinfunction "1_1") (pintype "passive"))
      (node (ref "IC1") (pin "GND") (pinfunction "GND_GND") (pintype "input"))
      (node (ref "IC2") (pin "18") (pinfunction "GND_18") (pintype "power_in"))
      (node (ref "IC2") (pin "21") (pinfunction "GND_21") (pintype "power_in"))
      (node (ref "IC2") (pin "25") (pinfunction "AGND_25") (pintype "power_in"))
      (node (ref "IC2") (pin "26") (pinfunction "TEST_26") (pintype "bidirectional"))
      (node (ref "IC2") (pin "7") (pinfunction "GND_7") (pintype "power_in"))
      (node (ref "IC3") (pin "11") (pinfunction "GND_11") (pintype "power_in"))
      (node (ref "IC3") (pin "32") (pinfunction "GND1_32") (pintype "power_in"))
      (node (ref "IC3") (pin "62") (pinfunction "GND2_62") (pintype "power_in"))
      (node (ref "IC3") (pin "81") (pinfunction "GND3_81") (pintype "power_in"))
      (node (ref "IC3") (pin "99") (pinfunction "AGND_99") (pintype "power_in"))
      (node (ref "ICSP") (pin "6") (pinfunction "6_6") (pintype "passive"))
      (node (ref "JP1") (pin "GND") (pinfunction "6_GND") (pintype "passive"))
      (node (ref "L2") (pin "1") (pinfunction "1_1") (pintype "passive"))
      (node (ref "ON") (pin "K") (pinfunction "C_K") (pintype "passive"))
      (node (ref "R2") (pin "2") (pinfunction "2_2") (pintype "passive"))
      (node (ref "R8") (pin "1") (pinfunction "1_1") (pintype "passive"))
      (node (ref "R9") (pin "2") (pinfunction "2_2") (pintype "passive"))
      (node (ref "STEPDRV1") (pin "3") (pinfunction "MS2_3") (pintype "input"))
      (node (ref "STEPDRV1") (pin "4") (pinfunction "MS3_4") (pintype "input"))
      (node (ref "STEPDRV1") (pin "9") (pinfunction "GND_9") (pintype "power_in"))
      (node (ref "STEPDRV2") (pin "3") (pinfunction "MS2_3") (pintype "input"))
      (node (ref "STEPDRV2") (pin "4") (pinfunction "MS3_4") (pintype "input"))
      (node (ref "STEPDRV2") (pin "9") (pinfunction "GND_9") (pintype "power_in"))
      (node (ref "STEPDRV3") (pin "3") (pinfunction "MS2_3") (pintype "input"))
      (node (ref "STEPDRV3") (pin "4") (pinfunction "MS3_4") (pintype "input"))
      (node (ref "STEPDRV3") (pin "9") (pinfunction "GND_9") (pintype "power_in"))
      (node (ref "STEPDRV4") (pin "3") (pinfunction "MS2_3") (pintype "input"))
      (node (ref "STEPDRV4") (pin "4") (pinfunction "MS3_4") (pintype "input"))
      (node (ref "STEPDRV4") (pin "9") (pinfunction "GND_9") (pintype "power_in"))
      (node (ref "STEPDRV5") (pin "3") (pinfunction "MS2_3") (pintype "input"))
      (node (ref "STEPDRV5") (pin "4") (pinfunction "MS3_4") (pintype "input"))
      (node (ref "STEPDRV5") (pin "9") (pinfunction "GND_9") (pintype "power_in"))
      (node (ref "STEPDRV6") (pin "3") (pinfunction "MS2_3") (pintype "input"))
      (node (ref "STEPDRV6") (pin "4") (pinfunction "MS3_4") (pintype "input"))
      (node (ref "STEPDRV6") (pin "9") (pinfunction "GND_9") (pintype "power_in"))
      (node (ref "STEPDRV7") (pin "3") (pinfunction "MS2_3") (pintype "input"))
      (node (ref "STEPDRV7") (pin "4") (pinfunction "MS3_4") (pintype "input"))
      (node (ref "STEPDRV7") (pin "9") (pinfunction "GND_9") (pintype "power_in"))
      (node (ref "STEPDRV8") (pin "3") (pinfunction "MS2_3") (pintype "input"))
      (node (ref "STEPDRV8") (pin "4") (pinfunction "MS3_4") (pintype "input"))
      (node (ref "STEPDRV8") (pin "9") (pinfunction "GND_9") (pintype "power_in"))
      (node (ref "U$1") (pin "GND") (pinfunction "GND_GND") (pintype "bidirectional"))
      (node (ref "X9") (pin "P$1") (pinfunction "1_P$1") (pintype "passive"))
    )
    (net (code "76") (name "Net-(D1-PadC)") (class "Default")
      (node (ref "D1") (pin "C") (pinfunction "C_C") (pintype "passive"))
      (node (ref "L3") (pin "2") (pinfunction "2_2") (pintype "passive"))
    )
    (net (code "77") (name "Net-(IC2-3V3OUT)") (class "Default")
      (node (ref "C12") (pin "2") (pinfunction "2_2") (pintype "passive"))
      (node (ref "IC2") (pin "17") (pinfunction "3V3OUT_17") (pintype "output"))
    )
    (net (code "78") (name "Net-(IC2-CBUS0)") (class "Default")
      (node (ref "IC2") (pin "23") (pinfunction "CBUS0_23") (pintype "bidirectional"))
      (node (ref "R4") (pin "2") (pinfunction "2_2") (pintype "passive"))
    )
    (net (code "79") (name "Net-(IC2-CBUS1)") (class "Default")
      (node (ref "IC2") (pin "22") (pinfunction "CBUS1_22") (pintype "bidirectional"))
      (node (ref "R5") (pin "2") (pinfunction "2_2") (pintype "passive"))
    )
    (net (code "80") (name "Net-(IC2-USBDM)") (class "Default")
      (node (ref "IC2") (pin "16") (pinfunction "USBDM_16") (pintype "bidirectional"))
      (node (ref "U$1") (pin "D-") (pinfunction "D-_D-") (pintype "bidirectional"))
    )
    (net (code "81") (name "Net-(IC2-USBDP)") (class "Default")
      (node (ref "IC2") (pin "15") (pinfunction "USBDP_15") (pintype "bidirectional"))
      (node (ref "U$1") (pin "D+") (pinfunction "D+_D+") (pintype "bidirectional"))
    )
    (net (code "82") (name "Net-(IC2-_CTS)") (class "Default")
      (node (ref "IC2") (pin "11") (pinfunction "_CTS_11") (pintype "input"))
      (node (ref "JP1") (pin "CTS") (pinfunction "5_CTS") (pintype "passive"))
      (node (ref "R8") (pin "2") (pinfunction "2_2") (pintype "passive"))
    )
    (net (code "83") (name "Net-(IC2-_RESET)") (class "Default")
      (node (ref "IC2") (pin "19") (pinfunction "_RESET_19") (pintype "input"))
      (node (ref "R2") (pin "1") (pinfunction "1_1") (pintype "passive"))
      (node (ref "R3") (pin "2") (pinfunction "2_2") (pintype "passive"))
    )
    (net (code "84") (name "Net-(L1-Pad2)") (class "Default")
      (node (ref "L1") (pin "2") (pinfunction "2_2") (pintype "passive"))
      (node (ref "U$1") (pin "VBUS") (pinfunction "VBUS_VBUS") (pintype "bidirectional"))
    )
    (net (code "85") (name "Net-(ON-PadA)") (class "Default")
      (node (ref "ON") (pin "A") (pinfunction "A_A") (pintype "passive"))
      (node (ref "R1") (pin "1") (pinfunction "1_1") (pintype "passive"))
    )
    (net (code "86") (name "Net-(R9-Pad1)") (class "Default")
      (node (ref "R9") (pin "1") (pinfunction "1_1") (pintype "passive"))
      (node (ref "S1") (pin "1") (pinfunction "1_1") (pintype "passive"))
    )
    (net (code "87") (name "Net-(RX-C)") (class "Default")
      (node (ref "R5") (pin "1") (pinfunction "1_1") (pintype "passive"))
      (node (ref "RX") (pin "K") (pinfunction "C_K") (pintype "passive"))
    )
    (net (code "88") (name "Net-(STEPDRV1-~{RESET})") (class "Default")
      (node (ref "STEPDRV1") (pin "5") (pinfunction "~{RESET}_5") (pintype "input"))
      (node (ref "STEPDRV1") (pin "6") (pinfunction "~{SLEEP}_6") (pintype "input"))
    )
    (net (code "89") (name "Net-(STEPDRV2-~{RESET})") (class "Default")
      (node (ref "STEPDRV2") (pin "5") (pinfunction "~{RESET}_5") (pintype "input"))
      (node (ref "STEPDRV2") (pin "6") (pinfunction "~{SLEEP}_6") (pintype "input"))
    )
    (net (code "90") (name "Net-(STEPDRV3-~{RESET})") (class "Default")
      (node (ref "STEPDRV3") (pin "5") (pinfunction "~{RESET}_5") (pintype "input"))
      (node (ref "STEPDRV3") (pin "6") (pinfunction "~{SLEEP}_6") (pintype "input"))
    )
    (net (code "91") (name "Net-(STEPDRV4-~{RESET})") (class "Default")
      (node (ref "STEPDRV4") (pin "5") (pinfunction "~{RESET}_5") (pintype "input"))
      (node (ref "STEPDRV4") (pin "6") (pinfunction "~{SLEEP}_6") (pintype "input"))
    )
    (net (code "92") (name "Net-(STEPDRV5-~{RESET})") (class "Default")
      (node (ref "STEPDRV5") (pin "5") (pinfunction "~{RESET}_5") (pintype "input"))
      (node (ref "STEPDRV5") (pin "6") (pinfunction "~{SLEEP}_6") (pintype "input"))
    )
    (net (code "93") (name "Net-(STEPDRV6-~{RESET})") (class "Default")
      (node (ref "STEPDRV6") (pin "5") (pinfunction "~{RESET}_5") (pintype "input"))
      (node (ref "STEPDRV6") (pin "6") (pinfunction "~{SLEEP}_6") (pintype "input"))
    )
    (net (code "94") (name "Net-(STEPDRV7-~{RESET})") (class "Default")
      (node (ref "STEPDRV7") (pin "5") (pinfunction "~{RESET}_5") (pintype "input"))
      (node (ref "STEPDRV7") (pin "6") (pinfunction "~{SLEEP}_6") (pintype "input"))
    )
    (net (code "95") (name "Net-(STEPDRV8-~{RESET})") (class "Default")
      (node (ref "STEPDRV8") (pin "5") (pinfunction "~{RESET}_5") (pintype "input"))
      (node (ref "STEPDRV8") (pin "6") (pinfunction "~{SLEEP}_6") (pintype "input"))
    )
    (net (code "96") (name "Net-(TX-C)") (class "Default")
      (node (ref "R4") (pin "1") (pinfunction "1_1") (pintype "passive"))
      (node (ref "TX") (pin "K") (pinfunction "C_K") (pintype "passive"))
    )
    (net (code "97") (name "Net-(U$1-MTN1)") (class "Default")
      (node (ref "C15") (pin "2") (pinfunction "2_2") (pintype "passive"))
      (node (ref "U$1") (pin "MTN1") (pinfunction "MTN2_MTN1") (pintype "bidirectional"))
      (node (ref "U$1") (pin "MTN2") (pinfunction "MTN3_MTN2") (pintype "bidirectional"))
      (node (ref "U$1") (pin "MTN3") (pinfunction "MTN1_MTN3") (pintype "bidirectional"))
      (node (ref "U$1") (pin "MTN4") (pinfunction "MTN4_MTN4") (pintype "bidirectional"))
    )
    (net (code "98") (name "unconnected-(IC2-CBUS2-Pad13)") (class "Default")
      (node (ref "IC2") (pin "13") (pinfunction "CBUS2_13") (pintype "bidirectional"))
    )
    (net (code "99") (name "unconnected-(IC2-CBUS3-Pad14)") (class "Default")
      (node (ref "IC2") (pin "14") (pinfunction "CBUS3_14") (pintype "bidirectional"))
    )
    (net (code "100") (name "unconnected-(IC2-CBUS4-Pad12)") (class "Default")
      (node (ref "IC2") (pin "12") (pinfunction "CBUS4_12") (pintype "bidirectional"))
    )
    (net (code "101") (name "unconnected-(IC2-NC-Pad8)") (class "Default")
      (node (ref "IC2") (pin "8") (pinfunction "NC_8") (pintype "no_connect"))
    )
    (net (code "102") (name "unconnected-(IC2-NC-Pad24)") (class "Default")
      (node (ref "IC2") (pin "24") (pinfunction "NC_24") (pintype "no_connect"))
    )
    (net (code "103") (name "unconnected-(IC2-OSCI-Pad27)") (class "Default")
      (node (ref "IC2") (pin "27") (pinfunction "OSCI_27") (pintype "input"))
    )
    (net (code "104") (name "unconnected-(IC2-OSCO-Pad28)") (class "Default")
      (node (ref "IC2") (pin "28") (pinfunction "OSCO_28") (pintype "output"))
    )
    (net (code "105") (name "unconnected-(IC2-_DCD-Pad10)") (class "Default")
      (node (ref "IC2") (pin "10") (pinfunction "_DCD_10") (pintype "input"))
    )
    (net (code "106") (name "unconnected-(IC2-_DSR-Pad9)") (class "Default")
      (node (ref "IC2") (pin "9") (pinfunction "_DSR_9") (pintype "input"))
    )
    (net (code "107") (name "unconnected-(IC2-_RI-Pad6)") (class "Default")
      (node (ref "IC2") (pin "6") (pinfunction "_RI_6") (pintype "input"))
    )
    (net (code "108") (name "unconnected-(IC2-_RTS-Pad3)") (class "Default")
      (node (ref "IC2") (pin "3") (pinfunction "_RTS_3") (pintype "output"))
    )
    (net (code "109") (name "unconnected-(IC3-(ADC0)PF0-Pad97)") (class "Default")
      (node (ref "IC3") (pin "97") (pinfunction "(ADC0)PF0_97") (pintype "bidirectional"))
    )
    (net (code "110") (name "unconnected-(IC3-(ADC1)PF1-Pad96)") (class "Default")
      (node (ref "IC3") (pin "96") (pinfunction "(ADC1)PF1_96") (pintype "bidirectional"))
    )
    (net (code "111") (name "unconnected-(IC3-(ADC2)PF2-Pad95)") (class "Default")
      (node (ref "IC3") (pin "95") (pinfunction "(ADC2)PF2_95") (pintype "bidirectional"))
    )
    (net (code "112") (name "unconnected-(IC3-(ADC3)PF3-Pad94)") (class "Default")
      (node (ref "IC3") (pin "94") (pinfunction "(ADC3)PF3_94") (pintype "bidirectional"))
    )
    (net (code "113") (name "unconnected-(IC3-(ADC4{slash}TCK)PF4-Pad93)") (class "Default")
      (node (ref "IC3") (pin "93") (pinfunction "(ADC4/TCK)PF4_93") (pintype "bidirectional"))
    )
    (net (code "114") (name "unconnected-(IC3-(ADC5{slash}TMS)PF5-Pad92)") (class "Default")
      (node (ref "IC3") (pin "92") (pinfunction "(ADC5/TMS)PF5_92") (pintype "bidirectional"))
    )
    (net (code "115") (name "unconnected-(IC3-(ADC6{slash}TDO)PF6-Pad91)") (class "Default")
      (node (ref "IC3") (pin "91") (pinfunction "(ADC6/TDO)PF6_91") (pintype "bidirectional"))
    )
    (net (code "116") (name "unconnected-(IC3-(ADC7{slash}TDI)PF7-Pad90)") (class "Default")
      (node (ref "IC3") (pin "90") (pinfunction "(ADC7/TDI)PF7_90") (pintype "bidirectional"))
    )
    (net (code "117") (name "unconnected-(IC3-(ALE)PG2-Pad70)") (class "Default")
      (node (ref "IC3") (pin "70") (pinfunction "(ALE)PG2_70") (pintype "bidirectional"))
    )
    (net (code "118") (name "unconnected-(IC3-(CLKO{slash}ICP3{slash}INT7)PE7-Pad9)") (class "Default")
      (node (ref "IC3") (pin "9") (pinfunction "(CLKO/ICP3/INT7)PE7_9") (pintype "bidirectional"))
    )
    (net (code "119") (name "unconnected-(IC3-(ICP1)PD4-Pad47)") (class "Default")
      (node (ref "IC3") (pin "47") (pinfunction "(ICP1)PD4_47") (pintype "bidirectional"))
    )
    (net (code "120") (name "unconnected-(IC3-(OC0A{slash}OC1C{slash}PCINT7)PB7-Pad26)") (class "Default")
      (node (ref "IC3") (pin "26") (pinfunction "(OC0A/OC1C/PCINT7)PB7_26") (pintype "bidirectional"))
    )
    (net (code "121") (name "unconnected-(IC3-(OC1B{slash}PCINT6)PB6-Pad25)") (class "Default")
      (node (ref "IC3") (pin "25") (pinfunction "(OC1B/PCINT6)PB6_25") (pintype "bidirectional"))
    )
    (net (code "122") (name "unconnected-(IC3-(RD)PG1-Pad52)") (class "Default")
      (node (ref "IC3") (pin "52") (pinfunction "(RD)PG1_52") (pintype "bidirectional"))
    )
    (net (code "123") (name "unconnected-(IC3-(RXD1{slash}INT2)PD2-Pad45)") (class "Default")
      (node (ref "IC3") (pin "45") (pinfunction "(RXD1/INT2)PD2_45") (pintype "bidirectional"))
    )
    (net (code "124") (name "unconnected-(IC3-(SCL{slash}INT0)PD0-Pad43)") (class "Default")
      (node (ref "IC3") (pin "43") (pinfunction "(SCL/INT0)PD0_43") (pintype "bidirectional"))
    )
    (net (code "125") (name "unconnected-(IC3-(SDA{slash}INT1)PD1-Pad44)") (class "Default")
      (node (ref "IC3") (pin "44") (pinfunction "(SDA/INT1)PD1_44") (pintype "bidirectional"))
    )
    (net (code "126") (name "unconnected-(IC3-(SS{slash}PCINT0)PB0-Pad19)") (class "Default")
      (node (ref "IC3") (pin "19") (pinfunction "(SS/PCINT0)PB0_19") (pintype "bidirectional"))
    )
    (net (code "127") (name "unconnected-(IC3-(T0)PD7-Pad50)") (class "Default")
      (node (ref "IC3") (pin "50") (pinfunction "(T0)PD7_50") (pintype "bidirectional"))
    )
    (net (code "128") (name "unconnected-(IC3-(T1)PD6-Pad49)") (class "Default")
      (node (ref "IC3") (pin "49") (pinfunction "(T1)PD6_49") (pintype "bidirectional"))
    )
    (net (code "129") (name "unconnected-(IC3-(T3{slash}INT6)PE6-Pad8)") (class "Default")
      (node (ref "IC3") (pin "8") (pinfunction "(T3/INT6)PE6_8") (pintype "bidirectional"))
    )
    (net (code "130") (name "unconnected-(IC3-(TOSC1)PG4-Pad29)") (class "Default")
      (node (ref "IC3") (pin "29") (pinfunction "(TOSC1)PG4_29") (pintype "bidirectional"))
    )
    (net (code "131") (name "unconnected-(IC3-(TOSC2)PG3-Pad28)") (class "Default")
      (node (ref "IC3") (pin "28") (pinfunction "(TOSC2)PG3_28") (pintype "bidirectional"))
    )
    (net (code "132") (name "unconnected-(IC3-(TXD1{slash}INT3)PD3-Pad46)") (class "Default")
      (node (ref "IC3") (pin "46") (pinfunction "(TXD1/INT3)PD3_46") (pintype "bidirectional"))
    )
    (net (code "133") (name "unconnected-(IC3-(WR)PG0-Pad51)") (class "Default")
      (node (ref "IC3") (pin "51") (pinfunction "(WR)PG0_51") (pintype "bidirectional"))
    )
    (net (code "134") (name "unconnected-(IC3-(XCK0{slash}AIN0)PE2-Pad4)") (class "Default")
      (node (ref "IC3") (pin "4") (pinfunction "(XCK0/AIN0)PE2_4") (pintype "bidirectional"))
    )
    (net (code "135") (name "unconnected-(IC3-(XCK1)PD5-Pad48)") (class "Default")
      (node (ref "IC3") (pin "48") (pinfunction "(XCK1)PD5_48") (pintype "bidirectional"))
    )
    (net (code "136") (name "unconnected-(IC3-PH0(RXD2)-Pad12)") (class "Default")
      (node (ref "IC3") (pin "12") (pinfunction "PH0(RXD2)_12") (pintype "bidirectional"))
    )
    (net (code "137") (name "unconnected-(IC3-PH1(TXD2)-Pad13)") (class "Default")
      (node (ref "IC3") (pin "13") (pinfunction "PH1(TXD2)_13") (pintype "bidirectional"))
    )
    (net (code "138") (name "unconnected-(IC3-PH2(XCK2)-Pad14)") (class "Default")
      (node (ref "IC3") (pin "14") (pinfunction "PH2(XCK2)_14") (pintype "bidirectional"))
    )
    (net (code "139") (name "unconnected-(IC3-PH7(T4)-Pad27)") (class "Default")
      (node (ref "IC3") (pin "27") (pinfunction "PH7(T4)_27") (pintype "bidirectional"))
    )
    (net (code "140") (name "unconnected-(IC3-PJ0(RXD3{slash}PCINT9)-Pad63)") (class "Default")
      (node (ref "IC3") (pin "63") (pinfunction "PJ0(RXD3/PCINT9)_63") (pintype "bidirectional"))
    )
    (net (code "141") (name "unconnected-(IC3-PJ1(TXD3{slash}PCINT10)-Pad64)") (class "Default")
      (node (ref "IC3") (pin "64") (pinfunction "PJ1(TXD3/PCINT10)_64") (pintype "bidirectional"))
    )
    (net (code "142") (name "unconnected-(IC3-PJ2(XCK3{slash}PCINT11)-Pad65)") (class "Default")
      (node (ref "IC3") (pin "65") (pinfunction "PJ2(XCK3/PCINT11)_65") (pintype "bidirectional"))
    )
    (net (code "143") (name "unconnected-(IC3-PJ3(PCINT12)-Pad66)") (class "Default")
      (node (ref "IC3") (pin "66") (pinfunction "PJ3(PCINT12)_66") (pintype "bidirectional"))
    )
    (net (code "144") (name "unconnected-(IC3-PJ4(PCINT13)-Pad67)") (class "Default")
      (node (ref "IC3") (pin "67") (pinfunction "PJ4(PCINT13)_67") (pintype "bidirectional"))
    )
    (net (code "145") (name "unconnected-(IC3-PJ5(PCINT14)-Pad68)") (class "Default")
      (node (ref "IC3") (pin "68") (pinfunction "PJ5(PCINT14)_68") (pintype "bidirectional"))
    )
    (net (code "146") (name "unconnected-(IC3-PJ6(PCINT15)-Pad69)") (class "Default")
      (node (ref "IC3") (pin "69") (pinfunction "PJ6(PCINT15)_69") (pintype "bidirectional"))
    )
    (net (code "147") (name "unconnected-(IC3-PJ7-Pad79)") (class "Default")
      (node (ref "IC3") (pin "79") (pinfunction "PJ7_79") (pintype "bidirectional"))
    )
    (net (code "148") (name "unconnected-(IC3-PK0(ADC8{slash}PCINT16)-Pad89)") (class "Default")
      (node (ref "IC3") (pin "89") (pinfunction "PK0(ADC8/PCINT16)_89") (pintype "bidirectional"))
    )
    (net (code "149") (name "unconnected-(IC3-PK1(ADC9{slash}PCINT17)-Pad88)") (class "Default")
      (node (ref "IC3") (pin "88") (pinfunction "PK1(ADC9/PCINT17)_88") (pintype "bidirectional"))
    )
    (net (code "150") (name "unconnected-(IC3-PK2(ADC10{slash}PCINT18)-Pad87)") (class "Default")
      (node (ref "IC3") (pin "87") (pinfunction "PK2(ADC10/PCINT18)_87") (pintype "bidirectional"))
    )
    (net (code "151") (name "unconnected-(IC3-PK3(ADC11{slash}PCINT19)-Pad86)") (class "Default")
      (node (ref "IC3") (pin "86") (pinfunction "PK3(ADC11/PCINT19)_86") (pintype "bidirectional"))
    )
    (net (code "152") (name "unconnected-(IC3-PK4(ADC12{slash}PCINT20)-Pad85)") (class "Default")
      (node (ref "IC3") (pin "85") (pinfunction "PK4(ADC12/PCINT20)_85") (pintype "bidirectional"))
    )
    (net (code "153") (name "unconnected-(IC3-PK5(ADC13{slash}PCINT21)-Pad84)") (class "Default")
      (node (ref "IC3") (pin "84") (pinfunction "PK5(ADC13/PCINT21)_84") (pintype "bidirectional"))
    )
    (net (code "154") (name "unconnected-(IC3-PK6(ADC14{slash}PCINT22)-Pad83)") (class "Default")
      (node (ref "IC3") (pin "83") (pinfunction "PK6(ADC14/PCINT22)_83") (pintype "bidirectional"))
    )
    (net (code "155") (name "unconnected-(IC3-PK7(ADC15{slash}PCINT23)-Pad82)") (class "Default")
      (node (ref "IC3") (pin "82") (pinfunction "PK7(ADC15/PCINT23)_82") (pintype "bidirectional"))
    )
    (net (code "156") (name "unconnected-(IC3-PL0(ICP4)-Pad35)") (class "Default")
      (node (ref "IC3") (pin "35") (pinfunction "PL0(ICP4)_35") (pintype "bidirectional"))
    )
    (net (code "157") (name "unconnected-(IC3-PL1(ICP5)-Pad36)") (class "Default")
      (node (ref "IC3") (pin "36") (pinfunction "PL1(ICP5)_36") (pintype "bidirectional"))
    )
    (net (code "158") (name "unconnected-(IC3-PL2(T5)-Pad37)") (class "Default")
      (node (ref "IC3") (pin "37") (pinfunction "PL2(T5)_37") (pintype "bidirectional"))
    )
    (net (code "159") (name "unconnected-(IC3-PL3(OC5A)-Pad38)") (class "Default")
      (node (ref "IC3") (pin "38") (pinfunction "PL3(OC5A)_38") (pintype "bidirectional"))
    )
    (net (code "160") (name "unconnected-(IC3-PL4(OC5B)-Pad39)") (class "Default")
      (node (ref "IC3") (pin "39") (pinfunction "PL4(OC5B)_39") (pintype "bidirectional"))
    )
    (net (code "161") (name "unconnected-(IC3-PL5(OC5C)-Pad40)") (class "Default")
      (node (ref "IC3") (pin "40") (pinfunction "PL5(OC5C)_40") (pintype "bidirectional"))
    )
    (net (code "162") (name "unconnected-(IC3-PL6-Pad41)") (class "Default")
      (node (ref "IC3") (pin "41") (pinfunction "PL6_41") (pintype "bidirectional"))
    )
    (net (code "163") (name "unconnected-(IC3-PL7-Pad42)") (class "Default")
      (node (ref "IC3") (pin "42") (pinfunction "PL7_42") (pintype "bidirectional"))
    )
    (net (code "164") (name "unconnected-(U$1-PadID)") (class "Default")
      (node (ref "U$1") (pin "ID") (pinfunction "ID_ID") (pintype "bidirectional"))
    )
  )
)
